# FabPOx.net
KiCad netlist of a schematic drawn in EAGLE
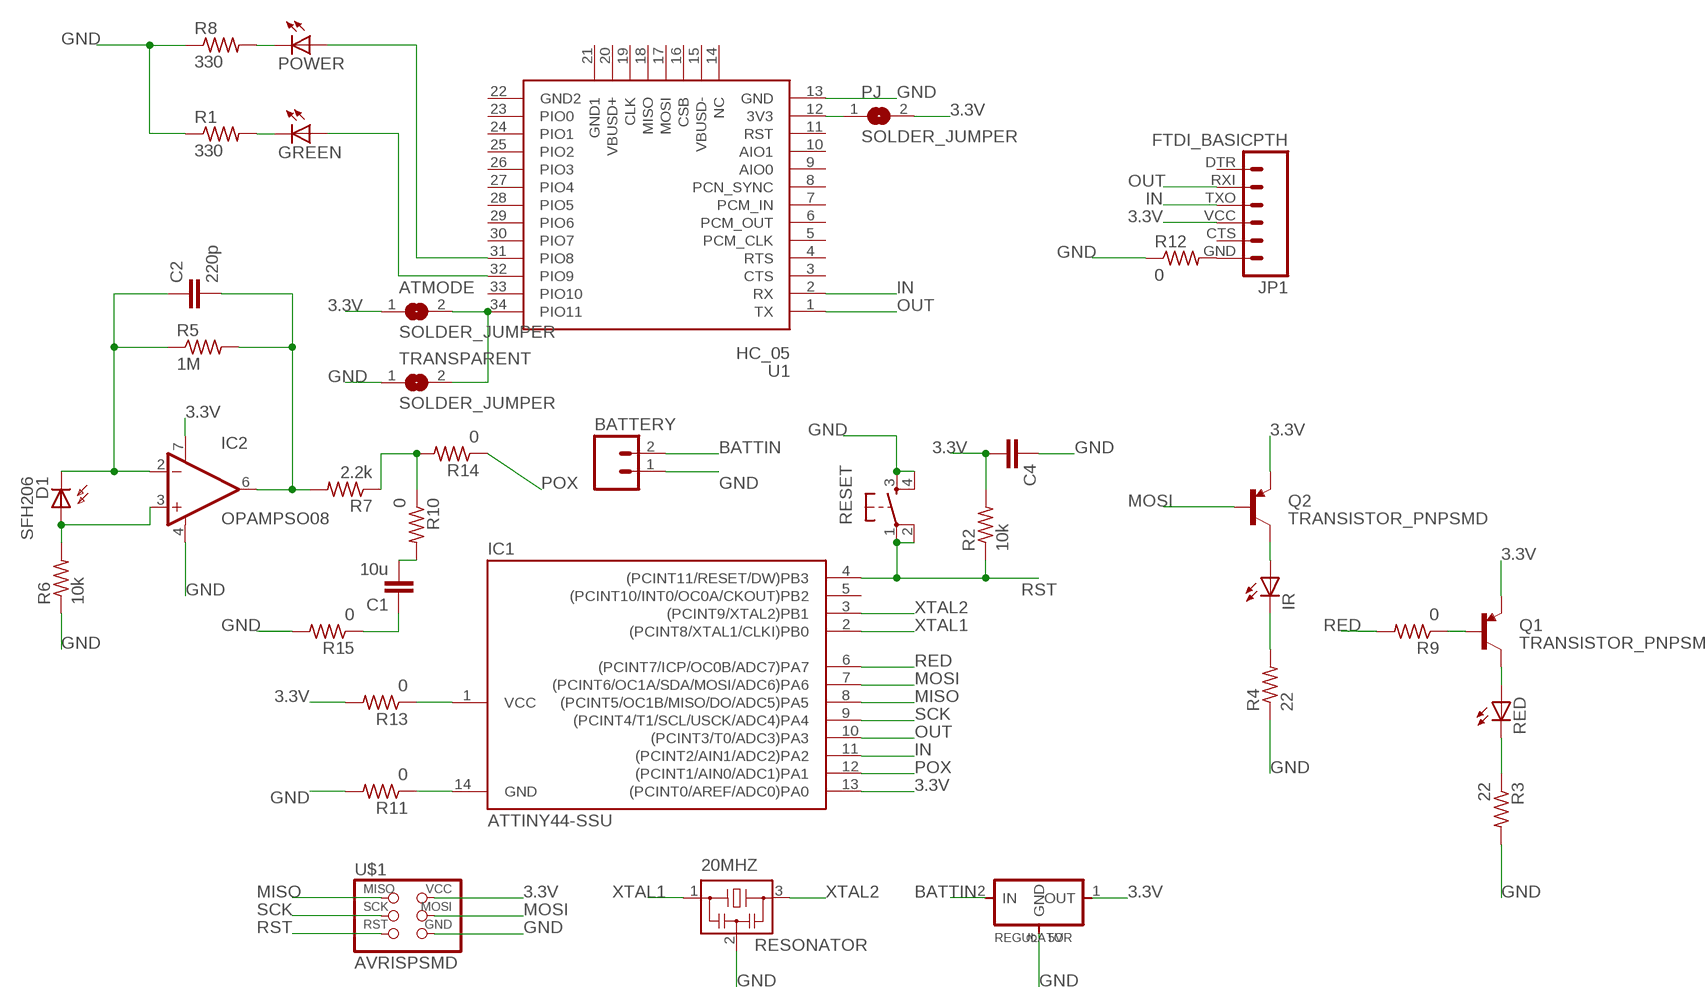
[diagram p0: schematic, sheet 1]

(export (version "E")
  (design (tool "Eeschema 10.0.6"))
  (components
    (comp (ref "20MHZ")
      (value "RESONATOR")
      (footprint "eagle-import:EFOBM")
      (libsource (lib "eagle-import") (part "RESONATOR"))
    )
    (comp (ref "ATMODE")
      (value "SOLDER_JUMPER")
      (footprint "eagle-import:SJFAB")
      (libsource (lib "eagle-import") (part "SOLDER_JUMPER"))
    )
    (comp (ref "BATTERY")
      (value "M02PTH")
      (footprint "eagle-import:1X02")
      (libsource (lib "eagle-import") (part "M02PTH"))
    )
    (comp (ref "C1")
      (value "10u")
      (footprint "eagle-import:1206")
      (libsource (lib "eagle-import") (part "CAP1206"))
    )
    (comp (ref "C2")
      (value "220p")
      (footprint "eagle-import:1206")
      (libsource (lib "eagle-import") (part "CAP1206"))
    )
    (comp (ref "C4")
      (value "CAP1206")
      (footprint "eagle-import:1206")
      (libsource (lib "eagle-import") (part "CAP1206"))
    )
    (comp (ref "D1")
      (value "SFH206")
      (footprint "eagle-import:SFH206")
      (fields (field (name "MPN") "SFH206K"))
      (libsource (lib "eagle-import") (part "SFH206"))
    )
    (comp (ref "GREEN")
      (value "LED1206")
      (footprint "eagle-import:1206")
      (libsource (lib "eagle-import") (part "ng_LED1206"))
    )
    (comp (ref "IC1")
      (value "ATTINY44-SSU")
      (footprint "eagle-import:SOIC14")
      (libsource (lib "eagle-import") (part "ATTINY44-SSU"))
    )
    (comp (ref "IC2")
      (value "OPAMPSO08")
      (footprint "eagle-import:SO08")
      (libsource (lib "eagle-import") (part "OPAMPSO08"))
    )
    (comp (ref "IR")
      (value "LED3MM")
      (footprint "eagle-import:LED3MM")
      (libsource (lib "eagle-import") (part "LED3MM"))
    )
    (comp (ref "JP1")
      (value "FTDI_BASICPTH")
      (footprint "eagle-import:FTDI_BASIC")
      (libsource (lib "eagle-import") (part "FTDI_BASICPTH"))
    )
    (comp (ref "PJ")
      (value "SOLDER_JUMPER")
      (footprint "eagle-import:SJFAB")
      (libsource (lib "eagle-import") (part "SOLDER_JUMPER"))
    )
    (comp (ref "POWER")
      (value "LED1206")
      (footprint "eagle-import:1206")
      (libsource (lib "eagle-import") (part "ng_LED1206"))
    )
    (comp (ref "Q1")
      (value "TRANSISTOR_PNPSMD")
      (footprint "eagle-import:SOT23-3")
      (libsource (lib "eagle-import") (part "TRANSISTOR_PNPSMD"))
    )
    (comp (ref "Q2")
      (value "TRANSISTOR_PNPSMD")
      (footprint "eagle-import:SOT23-3")
      (libsource (lib "eagle-import") (part "TRANSISTOR_PNPSMD"))
    )
    (comp (ref "R1")
      (value "330")
      (footprint "eagle-import:R1206")
      (libsource (lib "eagle-import") (part "RES-US1206"))
    )
    (comp (ref "R2")
      (value "10k")
      (footprint "eagle-import:R1206")
      (libsource (lib "eagle-import") (part "RES-US1206"))
    )
    (comp (ref "R3")
      (value "22")
      (footprint "eagle-import:R1206")
      (libsource (lib "eagle-import") (part "RES-US1206"))
    )
    (comp (ref "R4")
      (value "22")
      (footprint "eagle-import:R1206")
      (libsource (lib "eagle-import") (part "RES-US1206"))
    )
    (comp (ref "R5")
      (value "1M")
      (footprint "eagle-import:R1206")
      (libsource (lib "eagle-import") (part "RES-US1206"))
    )
    (comp (ref "R6")
      (value "10k")
      (footprint "eagle-import:R1206")
      (libsource (lib "eagle-import") (part "RES-US1206"))
    )
    (comp (ref "R7")
      (value "2.2k")
      (footprint "eagle-import:R1206")
      (libsource (lib "eagle-import") (part "RES-US1206"))
    )
    (comp (ref "R8")
      (value "330")
      (footprint "eagle-import:R1206")
      (libsource (lib "eagle-import") (part "RES-US1206"))
    )
    (comp (ref "R9")
      (value "0")
      (footprint "eagle-import:R1206")
      (libsource (lib "eagle-import") (part "RES-US1206"))
    )
    (comp (ref "R10")
      (value "0")
      (footprint "eagle-import:R1206")
      (libsource (lib "eagle-import") (part "RES-US1206"))
    )
    (comp (ref "R11")
      (value "0")
      (footprint "eagle-import:R1206")
      (libsource (lib "eagle-import") (part "RES-US1206"))
    )
    (comp (ref "R12")
      (value "0")
      (footprint "eagle-import:R1206")
      (libsource (lib "eagle-import") (part "RES-US1206"))
    )
    (comp (ref "R13")
      (value "0")
      (footprint "eagle-import:R1206")
      (libsource (lib "eagle-import") (part "RES-US1206"))
    )
    (comp (ref "R14")
      (value "0")
      (footprint "eagle-import:R1206")
      (libsource (lib "eagle-import") (part "RES-US1206"))
    )
    (comp (ref "R15")
      (value "0")
      (footprint "eagle-import:R1206")
      (libsource (lib "eagle-import") (part "RES-US1206"))
    )
    (comp (ref "RED")
      (value "LED3MM")
      (footprint "eagle-import:LED3MM")
      (libsource (lib "eagle-import") (part "LED3MM"))
    )
    (comp (ref "REGULATOR")
      (value "5V")
      (footprint "eagle-import:SOT23")
      (libsource (lib "eagle-import") (part "REGULATORSOT23"))
    )
    (comp (ref "RESET")
      (value "6MM_SWITCH6MM_SWITCH")
      (footprint "eagle-import:6MM_SWITCH")
      (libsource (lib "eagle-import") (part "6MM_SWITCH6MM_SWITCH"))
    )
    (comp (ref "TRANSPARENT")
      (value "SOLDER_JUMPER")
      (footprint "eagle-import:SJFAB")
      (libsource (lib "eagle-import") (part "SOLDER_JUMPER"))
    )
    (comp (ref "U$1")
      (value "AVRISPSMD")
      (footprint "eagle-import:2X03SMD")
      (libsource (lib "eagle-import") (part "AVRISPSMD"))
    )
    (comp (ref "U1")
      (value "HC_05")
      (footprint "eagle-import:BLUETOOTH_SMD")
      (libsource (lib "eagle-import") (part "HC_05"))
    )
  )
  (nets
    (net (code "1") (name "/3.3V") (class "Default")
      (node (ref "ATMODE") (pin "1") (pinfunction "1_1") (pintype "passive"))
      (node (ref "C4") (pin "2") (pinfunction "2_2") (pintype "passive"))
      (node (ref "IC1") (pin "13") (pinfunction "(PCINT0/AREF/ADC0)PA0_13") (pintype "bidirectional"))
      (node (ref "IC2") (pin "7") (pinfunction "V+_7") (pintype "power_in"))
      (node (ref "JP1") (pin "VCC") (pinfunction "4_VCC") (pintype "passive"))
      (node (ref "PJ") (pin "2") (pinfunction "2_2") (pintype "passive"))
      (node (ref "Q1") (pin "2") (pinfunction "E_2") (pintype "passive"))
      (node (ref "Q2") (pin "2") (pinfunction "E_2") (pintype "passive"))
      (node (ref "R13") (pin "2") (pinfunction "2_2") (pintype "passive"))
      (node (ref "R2") (pin "2") (pinfunction "2_2") (pintype "passive"))
      (node (ref "REGULATOR") (pin "1") (pinfunction "OUT_1") (pintype "bidirectional"))
      (node (ref "U$1") (pin "2") (pinfunction "VCC_2") (pintype "passive"))
    )
    (net (code "2") (name "/BATTIN") (class "Default")
      (node (ref "BATTERY") (pin "2") (pinfunction "2_2") (pintype "passive"))
      (node (ref "REGULATOR") (pin "2") (pinfunction "IN_2") (pintype "bidirectional"))
    )
    (net (code "3") (name "/GND") (class "Default")
      (node (ref "20MHZ") (pin "2") (pinfunction "2_2") (pintype "passive"))
      (node (ref "BATTERY") (pin "1") (pinfunction "1_1") (pintype "passive"))
      (node (ref "C4") (pin "1") (pinfunction "1_1") (pintype "passive"))
      (node (ref "IC2") (pin "4") (pinfunction "V-_4") (pintype "power_in"))
      (node (ref "IR") (pin "K") (pinfunction "C_K") (pintype "passive"))
      (node (ref "R1") (pin "1") (pinfunction "1_1") (pintype "passive"))
      (node (ref "R11") (pin "2") (pinfunction "2_2") (pintype "passive"))
      (node (ref "R12") (pin "1") (pinfunction "1_1") (pintype "passive"))
      (node (ref "R15") (pin "2") (pinfunction "2_2") (pintype "passive"))
      (node (ref "R3") (pin "1") (pinfunction "1_1") (pintype "passive"))
      (node (ref "R3") (pin "2") (pinfunction "2_2") (pintype "passive"))
      (node (ref "R4") (pin "1") (pinfunction "1_1") (pintype "passive"))
      (node (ref "R4") (pin "2") (pinfunction "2_2") (pintype "passive"))
      (node (ref "R6") (pin "1") (pinfunction "1_1") (pintype "passive"))
      (node (ref "R8") (pin "1") (pinfunction "1_1") (pintype "passive"))
      (node (ref "RED") (pin "K") (pinfunction "C_K") (pintype "passive"))
      (node (ref "REGULATOR") (pin "3") (pinfunction "GND_3") (pintype "bidirectional"))
      (node (ref "RESET") (pin "3") (pinfunction "S_3") (pintype "passive"))
      (node (ref "RESET") (pin "4") (pinfunction "S1_4") (pintype "passive"))
      (node (ref "TRANSPARENT") (pin "1") (pinfunction "1_1") (pintype "passive"))
      (node (ref "U$1") (pin "6") (pinfunction "GND_6") (pintype "passive"))
      (node (ref "U1") (pin "13") (pinfunction "GND_13") (pintype "bidirectional"))
    )
    (net (code "4") (name "/IN") (class "Default")
      (node (ref "IC1") (pin "11") (pinfunction "(PCINT2/AIN1/ADC2)PA2_11") (pintype "bidirectional"))
      (node (ref "JP1") (pin "TXO") (pinfunction "3_TXO") (pintype "passive"))
      (node (ref "U1") (pin "2") (pinfunction "RX_2") (pintype "bidirectional"))
    )
    (net (code "5") (name "/MISO") (class "Default")
      (node (ref "IC1") (pin "8") (pinfunction "(PCINT5/OC1B/MISO/DO/ADC5)PA5_8") (pintype "bidirectional"))
      (node (ref "U$1") (pin "1") (pinfunction "MISO_1") (pintype "passive"))
    )
    (net (code "6") (name "/MOSI") (class "Default")
      (node (ref "IC1") (pin "7") (pinfunction "(PCINT6/OC1A/SDA/MOSI/ADC6)PA6_7") (pintype "bidirectional"))
      (node (ref "Q2") (pin "1") (pinfunction "B_1") (pintype "passive"))
      (node (ref "U$1") (pin "4") (pinfunction "MOSI_4") (pintype "passive"))
    )
    (net (code "7") (name "/OUT") (class "Default")
      (node (ref "IC1") (pin "10") (pinfunction "(PCINT3/T0/ADC3)PA3_10") (pintype "bidirectional"))
      (node (ref "JP1") (pin "RXI") (pinfunction "2_RXI") (pintype "passive"))
      (node (ref "U1") (pin "1") (pinfunction "TX_1") (pintype "bidirectional"))
    )
    (net (code "8") (name "/POX") (class "Default")
      (node (ref "IC1") (pin "12") (pinfunction "(PCINT1/AIN0/ADC1)PA1_12") (pintype "bidirectional"))
      (node (ref "R14") (pin "1") (pinfunction "1_1") (pintype "passive"))
    )
    (net (code "9") (name "/RED") (class "Default")
      (node (ref "IC1") (pin "6") (pinfunction "(PCINT7/ICP/OC0B/ADC7)PA7_6") (pintype "bidirectional"))
      (node (ref "R9") (pin "2") (pinfunction "2_2") (pintype "passive"))
    )
    (net (code "10") (name "/RST") (class "Default")
      (node (ref "IC1") (pin "4") (pinfunction "(PCINT11/RESET/DW)PB3_4") (pintype "bidirectional"))
      (node (ref "R2") (pin "1") (pinfunction "1_1") (pintype "passive"))
      (node (ref "RESET") (pin "1") (pinfunction "P_1") (pintype "passive"))
      (node (ref "RESET") (pin "2") (pinfunction "P1_2") (pintype "passive"))
      (node (ref "U$1") (pin "5") (pinfunction "RST_5") (pintype "passive"))
    )
    (net (code "11") (name "/SCK") (class "Default")
      (node (ref "IC1") (pin "9") (pinfunction "(PCINT4/T1/SCL/USCK/ADC4)PA4_9") (pintype "bidirectional"))
      (node (ref "U$1") (pin "3") (pinfunction "SCK_3") (pintype "passive"))
    )
    (net (code "12") (name "/XTAL1") (class "Default")
      (node (ref "20MHZ") (pin "1") (pinfunction "1_1") (pintype "passive"))
      (node (ref "IC1") (pin "2") (pinfunction "(PCINT8/XTAL1/CLKI)PB0_2") (pintype "bidirectional"))
    )
    (net (code "13") (name "/XTAL2") (class "Default")
      (node (ref "20MHZ") (pin "3") (pinfunction "3_3") (pintype "passive"))
      (node (ref "IC1") (pin "3") (pinfunction "(PCINT9/XTAL2)PB1_3") (pintype "bidirectional"))
    )
    (net (code "14") (name "Net-(C1-Pad1)") (class "Default")
      (node (ref "C1") (pin "1") (pinfunction "1_1") (pintype "passive"))
      (node (ref "R15") (pin "1") (pinfunction "1_1") (pintype "passive"))
    )
    (net (code "15") (name "Net-(C1-Pad2)") (class "Default")
      (node (ref "C1") (pin "2") (pinfunction "2_2") (pintype "passive"))
      (node (ref "R10") (pin "2") (pinfunction "2_2") (pintype "passive"))
    )
    (net (code "16") (name "Net-(D1-C)") (class "Default")
      (node (ref "C2") (pin "1") (pinfunction "1_1") (pintype "passive"))
      (node (ref "D1") (pin "K") (pinfunction "C_K") (pintype "passive"))
      (node (ref "IC2") (pin "2") (pinfunction "-IN_2") (pintype "input"))
      (node (ref "R5") (pin "1") (pinfunction "1_1") (pintype "passive"))
    )
    (net (code "17") (name "Net-(GREEN-A)") (class "Default")
      (node (ref "GREEN") (pin "1") (pinfunction "A_1") (pintype "passive"))
      (node (ref "U1") (pin "32") (pinfunction "PIO9_32") (pintype "bidirectional"))
    )
    (net (code "18") (name "Net-(GREEN-C)") (class "Default")
      (node (ref "GREEN") (pin "2") (pinfunction "C_2") (pintype "passive"))
      (node (ref "R1") (pin "2") (pinfunction "2_2") (pintype "passive"))
    )
    (net (code "19") (name "Net-(IC1-GND)") (class "Default")
      (node (ref "IC1") (pin "14") (pinfunction "GND_14") (pintype "power_in"))
      (node (ref "R11") (pin "1") (pinfunction "1_1") (pintype "passive"))
    )
    (net (code "20") (name "Net-(IC1-VCC)") (class "Default")
      (node (ref "IC1") (pin "1") (pinfunction "VCC_1") (pintype "power_in"))
      (node (ref "R13") (pin "1") (pinfunction "1_1") (pintype "passive"))
    )
    (net (code "21") (name "Net-(IC2-+IN)") (class "Default")
      (node (ref "D1") (pin "A") (pinfunction "A_A") (pintype "passive"))
      (node (ref "IC2") (pin "3") (pinfunction "+IN_3") (pintype "input"))
      (node (ref "R6") (pin "2") (pinfunction "2_2") (pintype "passive"))
    )
    (net (code "22") (name "Net-(IC2-OUT)") (class "Default")
      (node (ref "C2") (pin "2") (pinfunction "2_2") (pintype "passive"))
      (node (ref "IC2") (pin "6") (pinfunction "OUT_6") (pintype "output"))
      (node (ref "R5") (pin "2") (pinfunction "2_2") (pintype "passive"))
      (node (ref "R7") (pin "2") (pinfunction "2_2") (pintype "passive"))
    )
    (net (code "23") (name "Net-(JP1-6)") (class "Default")
      (node (ref "JP1") (pin "GND") (pinfunction "6_GND") (pintype "passive"))
      (node (ref "R12") (pin "2") (pinfunction "2_2") (pintype "passive"))
    )
    (net (code "24") (name "Net-(POWER-A)") (class "Default")
      (node (ref "POWER") (pin "1") (pinfunction "A_1") (pintype "passive"))
      (node (ref "U1") (pin "31") (pinfunction "PIO8_31") (pintype "bidirectional"))
    )
    (net (code "25") (name "Net-(POWER-C)") (class "Default")
      (node (ref "POWER") (pin "2") (pinfunction "C_2") (pintype "passive"))
      (node (ref "R8") (pin "2") (pinfunction "2_2") (pintype "passive"))
    )
    (net (code "26") (name "Net-(Q1-B)") (class "Default")
      (node (ref "Q1") (pin "1") (pinfunction "B_1") (pintype "passive"))
      (node (ref "R9") (pin "1") (pinfunction "1_1") (pintype "passive"))
    )
    (net (code "27") (name "Net-(Q1-C)") (class "Default")
      (node (ref "Q1") (pin "3") (pinfunction "C_3") (pintype "passive"))
      (node (ref "RED") (pin "A") (pinfunction "A_A") (pintype "passive"))
    )
    (net (code "28") (name "Net-(Q2-C)") (class "Default")
      (node (ref "IR") (pin "A") (pinfunction "A_A") (pintype "passive"))
      (node (ref "Q2") (pin "3") (pinfunction "C_3") (pintype "passive"))
    )
    (net (code "29") (name "Net-(R10-Pad1)") (class "Default")
      (node (ref "R10") (pin "1") (pinfunction "1_1") (pintype "passive"))
      (node (ref "R14") (pin "2") (pinfunction "2_2") (pintype "passive"))
      (node (ref "R7") (pin "1") (pinfunction "1_1") (pintype "passive"))
    )
    (net (code "30") (name "Net-(U1-3V3)") (class "Default")
      (node (ref "PJ") (pin "1") (pinfunction "1_1") (pintype "passive"))
      (node (ref "U1") (pin "12") (pinfunction "3V3_12") (pintype "bidirectional"))
    )
    (net (code "31") (name "Net-(U1-PIO11)") (class "Default")
      (node (ref "ATMODE") (pin "2") (pinfunction "2_2") (pintype "passive"))
      (node (ref "TRANSPARENT") (pin "2") (pinfunction "2_2") (pintype "passive"))
      (node (ref "U1") (pin "34") (pinfunction "PIO11_34") (pintype "bidirectional"))
    )
    (net (code "32") (name "unconnected-(IC1-(PCINT10{slash}INT0{slash}OC0A{slash}CKOUT)PB2-Pad5)") (class "Default")
      (node (ref "IC1") (pin "5") (pinfunction "(PCINT10/INT0/OC0A/CKOUT)PB2_5") (pintype "bidirectional"))
    )
    (net (code "33") (name "unconnected-(JP1-1-PadDTR)") (class "Default")
      (node (ref "JP1") (pin "DTR") (pinfunction "1_DTR") (pintype "passive"))
    )
    (net (code "34") (name "unconnected-(JP1-5-PadCTS)") (class "Default")
      (node (ref "JP1") (pin "CTS") (pinfunction "5_CTS") (pintype "passive"))
    )
    (net (code "35") (name "unconnected-(U1-AIO0-Pad9)") (class "Default")
      (node (ref "U1") (pin "9") (pinfunction "AIO0_9") (pintype "bidirectional"))
    )
    (net (code "36") (name "unconnected-(U1-AIO1-Pad10)") (class "Default")
      (node (ref "U1") (pin "10") (pinfunction "AIO1_10") (pintype "bidirectional"))
    )
    (net (code "37") (name "unconnected-(U1-CLK-Pad19)") (class "Default")
      (node (ref "U1") (pin "19") (pinfunction "CLK_19") (pintype "bidirectional"))
    )
    (net (code "38") (name "unconnected-(U1-CSB-Pad16)") (class "Default")
      (node (ref "U1") (pin "16") (pinfunction "CSB_16") (pintype "bidirectional"))
    )
    (net (code "39") (name "unconnected-(U1-CTS-Pad3)") (class "Default")
      (node (ref "U1") (pin "3") (pinfunction "CTS_3") (pintype "bidirectional"))
    )
    (net (code "40") (name "unconnected-(U1-GND1-Pad21)") (class "Default")
      (node (ref "U1") (pin "21") (pinfunction "GND1_21") (pintype "bidirectional"))
    )
    (net (code "41") (name "unconnected-(U1-GND2-Pad22)") (class "Default")
      (node (ref "U1") (pin "22") (pinfunction "GND2_22") (pintype "bidirectional"))
    )
    (net (code "42") (name "unconnected-(U1-MISO-Pad18)") (class "Default")
      (node (ref "U1") (pin "18") (pinfunction "MISO_18") (pintype "bidirectional"))
    )
    (net (code "43") (name "unconnected-(U1-MOSI-Pad17)") (class "Default")
      (node (ref "U1") (pin "17") (pinfunction "MOSI_17") (pintype "bidirectional"))
    )
    (net (code "44") (name "unconnected-(U1-NC-Pad14)") (class "Default")
      (node (ref "U1") (pin "14") (pinfunction "NC_14") (pintype "bidirectional"))
    )
    (net (code "45") (name "unconnected-(U1-PCM_CLK-Pad5)") (class "Default")
      (node (ref "U1") (pin "5") (pinfunction "PCM_CLK_5") (pintype "bidirectional"))
    )
    (net (code "46") (name "unconnected-(U1-PCM_IN-Pad7)") (class "Default")
      (node (ref "U1") (pin "7") (pinfunction "PCM_IN_7") (pintype "bidirectional"))
    )
    (net (code "47") (name "unconnected-(U1-PCM_OUT-Pad6)") (class "Default")
      (node (ref "U1") (pin "6") (pinfunction "PCM_OUT_6") (pintype "bidirectional"))
    )
    (net (code "48") (name "unconnected-(U1-PCN_SYNC-Pad8)") (class "Default")
      (node (ref "U1") (pin "8") (pinfunction "PCN_SYNC_8") (pintype "bidirectional"))
    )
    (net (code "49") (name "unconnected-(U1-PIO0-Pad23)") (class "Default")
      (node (ref "U1") (pin "23") (pinfunction "PIO0_23") (pintype "bidirectional"))
    )
    (net (code "50") (name "unconnected-(U1-PIO1-Pad24)") (class "Default")
      (node (ref "U1") (pin "24") (pinfunction "PIO1_24") (pintype "bidirectional"))
    )
    (net (code "51") (name "unconnected-(U1-PIO2-Pad25)") (class "Default")
      (node (ref "U1") (pin "25") (pinfunction "PIO2_25") (pintype "bidirectional"))
    )
    (net (code "52") (name "unconnected-(U1-PIO3-Pad26)") (class "Default")
      (node (ref "U1") (pin "26") (pinfunction "PIO3_26") (pintype "bidirectional"))
    )
    (net (code "53") (name "unconnected-(U1-PIO4-Pad27)") (class "Default")
      (node (ref "U1") (pin "27") (pinfunction "PIO4_27") (pintype "bidirectional"))
    )
    (net (code "54") (name "unconnected-(U1-PIO5-Pad28)") (class "Default")
      (node (ref "U1") (pin "28") (pinfunction "PIO5_28") (pintype "bidirectional"))
    )
    (net (code "55") (name "unconnected-(U1-PIO6-Pad29)") (class "Default")
      (node (ref "U1") (pin "29") (pinfunction "PIO6_29") (pintype "bidirectional"))
    )
    (net (code "56") (name "unconnected-(U1-PIO7-Pad30)") (class "Default")
      (node (ref "U1") (pin "30") (pinfunction "PIO7_30") (pintype "bidirectional"))
    )
    (net (code "57") (name "unconnected-(U1-PIO10-Pad33)") (class "Default")
      (node (ref "U1") (pin "33") (pinfunction "PIO10_33") (pintype "bidirectional"))
    )
    (net (code "58") (name "unconnected-(U1-RST-Pad11)") (class "Default")
      (node (ref "U1") (pin "11") (pinfunction "RST_11") (pintype "bidirectional"))
    )
    (net (code "59") (name "unconnected-(U1-RTS-Pad4)") (class "Default")
      (node (ref "U1") (pin "4") (pinfunction "RTS_4") (pintype "bidirectional"))
    )
    (net (code "60") (name "unconnected-(U1-VBUSD+-Pad20)") (class "Default")
      (node (ref "U1") (pin "20") (pinfunction "VBUSD+_20") (pintype "bidirectional"))
    )
    (net (code "61") (name "unconnected-(U1-VBUSD--Pad15)") (class "Default")
      (node (ref "U1") (pin "15") (pinfunction "VBUSD-_15") (pintype "bidirectional"))
    )
  )
)
